# Vesta_wifi_power_3v3_1v8.net
KiCad netlist of a schematic drawn in Altium Designer
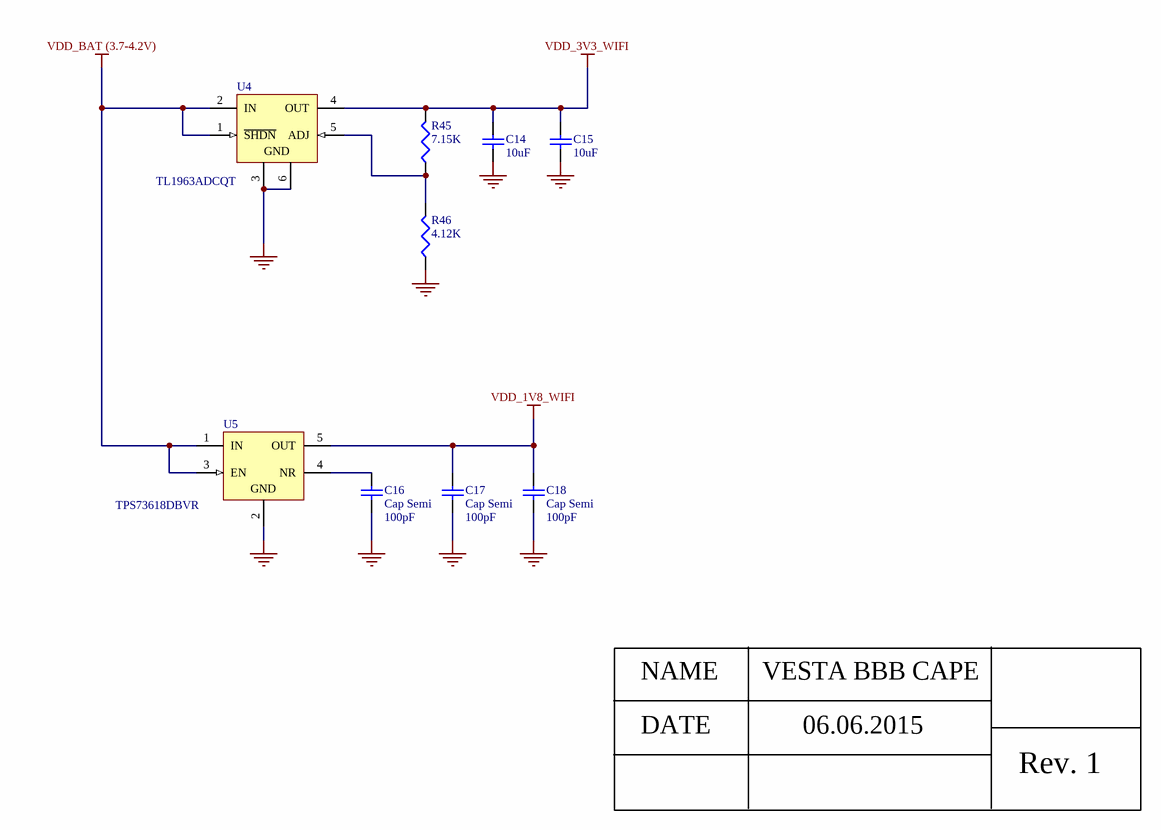
[diagram p0: Vesta_wifi_power_3v3_1v8.SchDoc]

(export (version "E")
  (design (tool "Eeschema 10.0.6"))
  (components
    (comp (ref "C14")
      (value "10uF")
      (footprint "C1206")
      (description "Capacitor (Semiconductor SIM Model)")
      (fields (field (name "PUBLISHER") "Altium Limited"))
      (libsource (lib "Miscellaneous Devices") (part "Cap Semi"))
    )
    (comp (ref "C15")
      (value "10uF")
      (footprint "C1206")
      (description "Capacitor (Semiconductor SIM Model)")
      (fields (field (name "PUBLISHER") "Altium Limited"))
      (libsource (lib "Miscellaneous Devices") (part "Cap Semi"))
    )
    (comp (ref "C16")
      (value "Cap Semi")
      (footprint "C1206")
      (description "Capacitor (Semiconductor SIM Model)")
      (fields (field (name "ALTIUM_VALUE") "100pF") (field (name "PUBLISHER") "Altium Limited"))
      (libsource (lib "Miscellaneous Devices") (part "Cap Semi"))
    )
    (comp (ref "C17")
      (value "Cap Semi")
      (footprint "C1206")
      (description "Capacitor (Semiconductor SIM Model)")
      (fields (field (name "ALTIUM_VALUE") "100pF") (field (name "PUBLISHER") "Altium Limited"))
      (libsource (lib "Miscellaneous Devices") (part "Cap Semi"))
    )
    (comp (ref "C18")
      (value "Cap Semi")
      (footprint "C1206")
      (description "Capacitor (Semiconductor SIM Model)")
      (fields (field (name "ALTIUM_VALUE") "100pF") (field (name "PUBLISHER") "Altium Limited"))
      (libsource (lib "Miscellaneous Devices") (part "Cap Semi"))
    )
    (comp (ref "R45")
      (value "7.15K")
      (footprint "J1-0603")
      (description "Resistor")
      (fields (field (name "PUBLISHER") "Altium Limited"))
      (libsource (lib "Miscellaneous Devices") (part "Res3"))
    )
    (comp (ref "R46")
      (value "4.12K")
      (footprint "J1-0603")
      (description "Resistor")
      (fields (field (name "PUBLISHER") "Altium Limited"))
      (libsource (lib "Miscellaneous Devices") (part "Res3"))
    )
    (comp (ref "U4")
      (value "TL1963ADCQT")
      (footprint "TI-DCQ6_M")
      (fields (field (name "MANUFACTURER") "Texas Instruments"))
      (libsource (lib "Altium Content Vault") (part "TI-TPS7A4501_TL1963A-6"))
    )
    (comp (ref "U5")
      (value "TPS73618DBVR")
      (footprint "TI-DBV5_N")
      (fields (field (name "MANUFACTURER") "Texas Instruments"))
      (libsource (lib "Altium Content Vault") (part "TI-TPS79NXX-YYSOT5"))
    )
  )
  (nets
    (net (code "1") (name "GND") (class "Default")
      (node (ref "C14") (pin "1") (pinfunction "1_1") (pintype "passive"))
      (node (ref "C15") (pin "1") (pinfunction "1_1") (pintype "passive"))
      (node (ref "C16") (pin "1") (pinfunction "1_1") (pintype "passive"))
      (node (ref "C17") (pin "1") (pinfunction "1_1") (pintype "passive"))
      (node (ref "C18") (pin "1") (pinfunction "1_1") (pintype "passive"))
      (node (ref "R46") (pin "1") (pinfunction "1_1") (pintype "passive"))
      (node (ref "U4") (pin "3") (pinfunction "GND_3") (pintype "power_in"))
      (node (ref "U4") (pin "6") (pinfunction "GND_6") (pintype "power_in"))
      (node (ref "U5") (pin "2") (pinfunction "GND_2") (pintype "power_in"))
    )
    (net (code "2") (name "Net-(U4-ADJ)") (class "Default")
      (node (ref "R45") (pin "1") (pinfunction "1_1") (pintype "passive"))
      (node (ref "R46") (pin "2") (pinfunction "2_2") (pintype "passive"))
      (node (ref "U4") (pin "5") (pinfunction "ADJ_5") (pintype "input"))
    )
    (net (code "3") (name "Net-(U5-NR)") (class "Default")
      (node (ref "C16") (pin "2") (pinfunction "2_2") (pintype "passive"))
      (node (ref "U5") (pin "4") (pinfunction "NR_4") (pintype "passive"))
    )
    (net (code "4") (name "VDD_1V8_WIFI") (class "Default")
      (node (ref "C17") (pin "2") (pinfunction "2_2") (pintype "passive"))
      (node (ref "C18") (pin "2") (pinfunction "2_2") (pintype "passive"))
      (node (ref "U5") (pin "5") (pinfunction "OUT_5") (pintype "power_in"))
    )
    (net (code "5") (name "VDD_3V3_WIFI") (class "Default")
      (node (ref "C14") (pin "2") (pinfunction "2_2") (pintype "passive"))
      (node (ref "C15") (pin "2") (pinfunction "2_2") (pintype "passive"))
      (node (ref "R45") (pin "2") (pinfunction "2_2") (pintype "passive"))
      (node (ref "U4") (pin "4") (pinfunction "OUT_4") (pintype "power_in"))
    )
    (net (code "6") (name "VDD_BAT (3.7-4.2V)") (class "Default")
      (node (ref "U4") (pin "1") (pinfunction "~{SHDN}_1") (pintype "input"))
      (node (ref "U4") (pin "2") (pinfunction "IN_2") (pintype "power_in"))
      (node (ref "U5") (pin "1") (pinfunction "IN_1") (pintype "power_in"))
      (node (ref "U5") (pin "3") (pinfunction "EN_3") (pintype "input"))
    )
  )
)
